# main.net
KiCad netlist of a schematic drawn in EAGLE
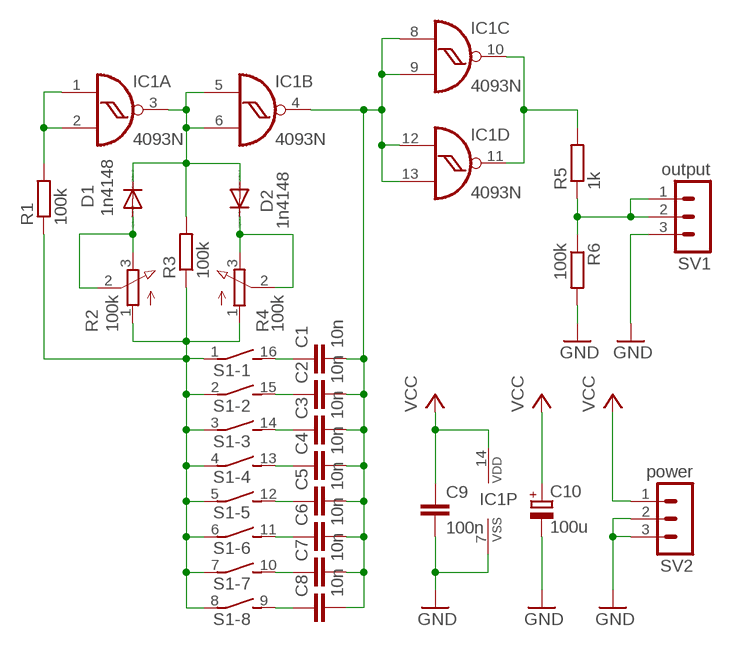
[diagram p0: schematic, sheet 1]

(export (version "E")
  (design (tool "Eeschema 10.0.6"))
  (components
    (comp (ref "C1")
      (value "10n")
      (footprint "eagle-import:C050-025X075")
      (libsource (lib "eagle-import") (part "C-EU050-025X075"))
    )
    (comp (ref "C2")
      (value "10n")
      (footprint "eagle-import:C050-025X075")
      (libsource (lib "eagle-import") (part "C-EU050-025X075"))
    )
    (comp (ref "C3")
      (value "10n")
      (footprint "eagle-import:C050-025X075")
      (libsource (lib "eagle-import") (part "C-EU050-025X075"))
    )
    (comp (ref "C4")
      (value "10n")
      (footprint "eagle-import:C050-025X075")
      (libsource (lib "eagle-import") (part "C-EU050-025X075"))
    )
    (comp (ref "C5")
      (value "10n")
      (footprint "eagle-import:C050-025X075")
      (libsource (lib "eagle-import") (part "C-EU050-025X075"))
    )
    (comp (ref "C6")
      (value "10n")
      (footprint "eagle-import:C050-025X075")
      (libsource (lib "eagle-import") (part "C-EU050-025X075"))
    )
    (comp (ref "C7")
      (value "10n")
      (footprint "eagle-import:C050-025X075")
      (libsource (lib "eagle-import") (part "C-EU050-025X075"))
    )
    (comp (ref "C8")
      (value "10n")
      (footprint "eagle-import:C050-025X075")
      (libsource (lib "eagle-import") (part "C-EU050-025X075"))
    )
    (comp (ref "C9")
      (value "100n")
      (footprint "eagle-import:C1206")
      (libsource (lib "eagle-import") (part "C-EUC1206"))
    )
    (comp (ref "C10")
      (value "100u")
      (footprint "eagle-import:E2,5-7")
      (libsource (lib "eagle-import") (part "CPOL-EUE2.5-7"))
    )
    (comp (ref "D1")
      (value "1n4148")
      (footprint "eagle-import:MINIMELF")
      (libsource (lib "eagle-import") (part "DIODE-MINIMELF"))
    )
    (comp (ref "D2")
      (value "1n4148")
      (footprint "eagle-import:MINIMELF")
      (libsource (lib "eagle-import") (part "DIODE-MINIMELF"))
    )
    (comp (ref "IC1")
      (value "4093N")
      (footprint "eagle-import:DIL14")
      (libsource (lib "eagle-import") (part "4093N"))
    )
    (comp (ref "R1")
      (value "100k")
      (footprint "eagle-import:0204V")
      (libsource (lib "eagle-import") (part "R-EU_0204/2V"))
    )
    (comp (ref "R2")
      (value "100k")
      (footprint "eagle-import:3RP_1610N")
      (libsource (lib "eagle-import") (part "3RP/1610N"))
    )
    (comp (ref "R3")
      (value "100k")
      (footprint "eagle-import:0204V")
      (libsource (lib "eagle-import") (part "R-EU_0204/2V"))
    )
    (comp (ref "R4")
      (value "100k")
      (footprint "eagle-import:3RP_1610N")
      (libsource (lib "eagle-import") (part "3RP/1610N"))
    )
    (comp (ref "R5")
      (value "1k")
      (footprint "eagle-import:0204V")
      (libsource (lib "eagle-import") (part "R-EU_0204/2V"))
    )
    (comp (ref "R6")
      (value "100k")
      (footprint "eagle-import:0204V")
      (libsource (lib "eagle-import") (part "R-EU_0204/2V"))
    )
    (comp (ref "S1")
      (value "DIP08S")
      (footprint "eagle-import:DIP08S")
      (libsource (lib "eagle-import") (part "DIP08S"))
    )
    (comp (ref "SV1")
      (value "output")
      (footprint "eagle-import:MA03-1")
      (libsource (lib "eagle-import") (part "MA03-1"))
    )
    (comp (ref "SV2")
      (value "power")
      (footprint "eagle-import:MA03-1")
      (libsource (lib "eagle-import") (part "MA03-1"))
    )
  )
  (nets
    (net (code "1") (name "GND") (class "Default")
      (node (ref "C10") (pin "-") (pinfunction "-_-") (pintype "passive"))
      (node (ref "C9") (pin "2") (pinfunction "2_2") (pintype "passive"))
      (node (ref "IC1") (pin "7") (pinfunction "VSS_7") (pintype "power_in"))
      (node (ref "R6") (pin "2") (pinfunction "2_2") (pintype "passive"))
      (node (ref "SV1") (pin "3") (pinfunction "3_3") (pintype "passive"))
      (node (ref "SV2") (pin "2") (pinfunction "2_2") (pintype "passive"))
      (node (ref "SV2") (pin "3") (pinfunction "3_3") (pintype "passive"))
    )
    (net (code "2") (name "Net-(IC1A-I0)") (class "Default")
      (node (ref "IC1") (pin "1") (pinfunction "I0_1") (pintype "input"))
      (node (ref "IC1") (pin "2") (pinfunction "I1_2") (pintype "input"))
      (node (ref "R1") (pin "2") (pinfunction "2_2") (pintype "passive"))
    )
    (net (code "3") (name "Net-(IC1A-O)") (class "Default")
      (node (ref "D1") (pin "C") (pinfunction "C_C") (pintype "passive"))
      (node (ref "D2") (pin "A") (pinfunction "A_A") (pintype "passive"))
      (node (ref "IC1") (pin "3") (pinfunction "O_3") (pintype "output"))
      (node (ref "IC1") (pin "5") (pinfunction "I0_5") (pintype "input"))
      (node (ref "IC1") (pin "6") (pinfunction "I1_6") (pintype "input"))
      (node (ref "R3") (pin "2") (pinfunction "2_2") (pintype "passive"))
    )
    (net (code "4") (name "Net-(IC1B-O)") (class "Default")
      (node (ref "C1") (pin "2") (pinfunction "2_2") (pintype "passive"))
      (node (ref "C2") (pin "2") (pinfunction "2_2") (pintype "passive"))
      (node (ref "C3") (pin "2") (pinfunction "2_2") (pintype "passive"))
      (node (ref "C4") (pin "2") (pinfunction "2_2") (pintype "passive"))
      (node (ref "C5") (pin "2") (pinfunction "2_2") (pintype "passive"))
      (node (ref "C6") (pin "2") (pinfunction "2_2") (pintype "passive"))
      (node (ref "C7") (pin "2") (pinfunction "2_2") (pintype "passive"))
      (node (ref "C8") (pin "2") (pinfunction "2_2") (pintype "passive"))
      (node (ref "IC1") (pin "12") (pinfunction "I0_12") (pintype "input"))
      (node (ref "IC1") (pin "13") (pinfunction "I1_13") (pintype "input"))
      (node (ref "IC1") (pin "4") (pinfunction "O_4") (pintype "output"))
      (node (ref "IC1") (pin "8") (pinfunction "I0_8") (pintype "input"))
      (node (ref "IC1") (pin "9") (pinfunction "I1_9") (pintype "input"))
    )
    (net (code "5") (name "Net-(IC1C-O)") (class "Default")
      (node (ref "IC1") (pin "10") (pinfunction "O_10") (pintype "output"))
      (node (ref "IC1") (pin "11") (pinfunction "O_11") (pintype "output"))
      (node (ref "R5") (pin "2") (pinfunction "2_2") (pintype "passive"))
    )
    (net (code "6") (name "Net-(R2-A)") (class "Default")
      (node (ref "R1") (pin "1") (pinfunction "1_1") (pintype "passive"))
      (node (ref "R2") (pin "1") (pinfunction "A_1") (pintype "passive"))
      (node (ref "R3") (pin "1") (pinfunction "1_1") (pintype "passive"))
      (node (ref "R4") (pin "1") (pinfunction "A_1") (pintype "passive"))
      (node (ref "S1") (pin "1") (pinfunction "1_1") (pintype "passive"))
      (node (ref "S1") (pin "2") (pinfunction "1_2") (pintype "passive"))
      (node (ref "S1") (pin "3") (pinfunction "1_3") (pintype "passive"))
      (node (ref "S1") (pin "4") (pinfunction "1_4") (pintype "passive"))
      (node (ref "S1") (pin "5") (pinfunction "1_5") (pintype "passive"))
      (node (ref "S1") (pin "6") (pinfunction "1_6") (pintype "passive"))
      (node (ref "S1") (pin "7") (pinfunction "1_7") (pintype "passive"))
      (node (ref "S1") (pin "8") (pinfunction "1_8") (pintype "passive"))
    )
    (net (code "7") (name "Net-(R2-E)") (class "Default")
      (node (ref "D1") (pin "A") (pinfunction "A_A") (pintype "passive"))
      (node (ref "R2") (pin "2") (pinfunction "S_2") (pintype "passive"))
      (node (ref "R2") (pin "3") (pinfunction "E_3") (pintype "passive"))
    )
    (net (code "8") (name "Net-(R4-E)") (class "Default")
      (node (ref "D2") (pin "C") (pinfunction "C_C") (pintype "passive"))
      (node (ref "R4") (pin "2") (pinfunction "S_2") (pintype "passive"))
      (node (ref "R4") (pin "3") (pinfunction "E_3") (pintype "passive"))
    )
    (net (code "9") (name "Net-(R5-Pad1)") (class "Default")
      (node (ref "R5") (pin "1") (pinfunction "1_1") (pintype "passive"))
      (node (ref "R6") (pin "1") (pinfunction "1_1") (pintype "passive"))
      (node (ref "SV1") (pin "1") (pinfunction "1_1") (pintype "passive"))
      (node (ref "SV1") (pin "2") (pinfunction "2_2") (pintype "passive"))
    )
    (net (code "10") (name "Net-(S1A-2)") (class "Default")
      (node (ref "C1") (pin "1") (pinfunction "1_1") (pintype "passive"))
      (node (ref "S1") (pin "16") (pinfunction "2_16") (pintype "passive"))
    )
    (net (code "11") (name "Net-(S1B-2)") (class "Default")
      (node (ref "C2") (pin "1") (pinfunction "1_1") (pintype "passive"))
      (node (ref "S1") (pin "15") (pinfunction "2_15") (pintype "passive"))
    )
    (net (code "12") (name "Net-(S1C-2)") (class "Default")
      (node (ref "C3") (pin "1") (pinfunction "1_1") (pintype "passive"))
      (node (ref "S1") (pin "14") (pinfunction "2_14") (pintype "passive"))
    )
    (net (code "13") (name "Net-(S1D-2)") (class "Default")
      (node (ref "C4") (pin "1") (pinfunction "1_1") (pintype "passive"))
      (node (ref "S1") (pin "13") (pinfunction "2_13") (pintype "passive"))
    )
    (net (code "14") (name "Net-(S1E-2)") (class "Default")
      (node (ref "C5") (pin "1") (pinfunction "1_1") (pintype "passive"))
      (node (ref "S1") (pin "12") (pinfunction "2_12") (pintype "passive"))
    )
    (net (code "15") (name "Net-(S1F-2)") (class "Default")
      (node (ref "C6") (pin "1") (pinfunction "1_1") (pintype "passive"))
      (node (ref "S1") (pin "11") (pinfunction "2_11") (pintype "passive"))
    )
    (net (code "16") (name "Net-(S1G-2)") (class "Default")
      (node (ref "C7") (pin "1") (pinfunction "1_1") (pintype "passive"))
      (node (ref "S1") (pin "10") (pinfunction "2_10") (pintype "passive"))
    )
    (net (code "17") (name "Net-(S1H-2)") (class "Default")
      (node (ref "C8") (pin "1") (pinfunction "1_1") (pintype "passive"))
      (node (ref "S1") (pin "9") (pinfunction "2_9") (pintype "passive"))
    )
    (net (code "18") (name "VCC") (class "Default")
      (node (ref "C10") (pin "+") (pinfunction "+_+") (pintype "passive"))
      (node (ref "C9") (pin "1") (pinfunction "1_1") (pintype "passive"))
      (node (ref "IC1") (pin "14") (pinfunction "VDD_14") (pintype "power_in"))
      (node (ref "SV2") (pin "1") (pinfunction "1_1") (pintype "passive"))
    )
  )
)
